# GECBalloonMCUFlightBoard_REV2_0_11-23-18.net
KiCad netlist of a schematic drawn in EAGLE
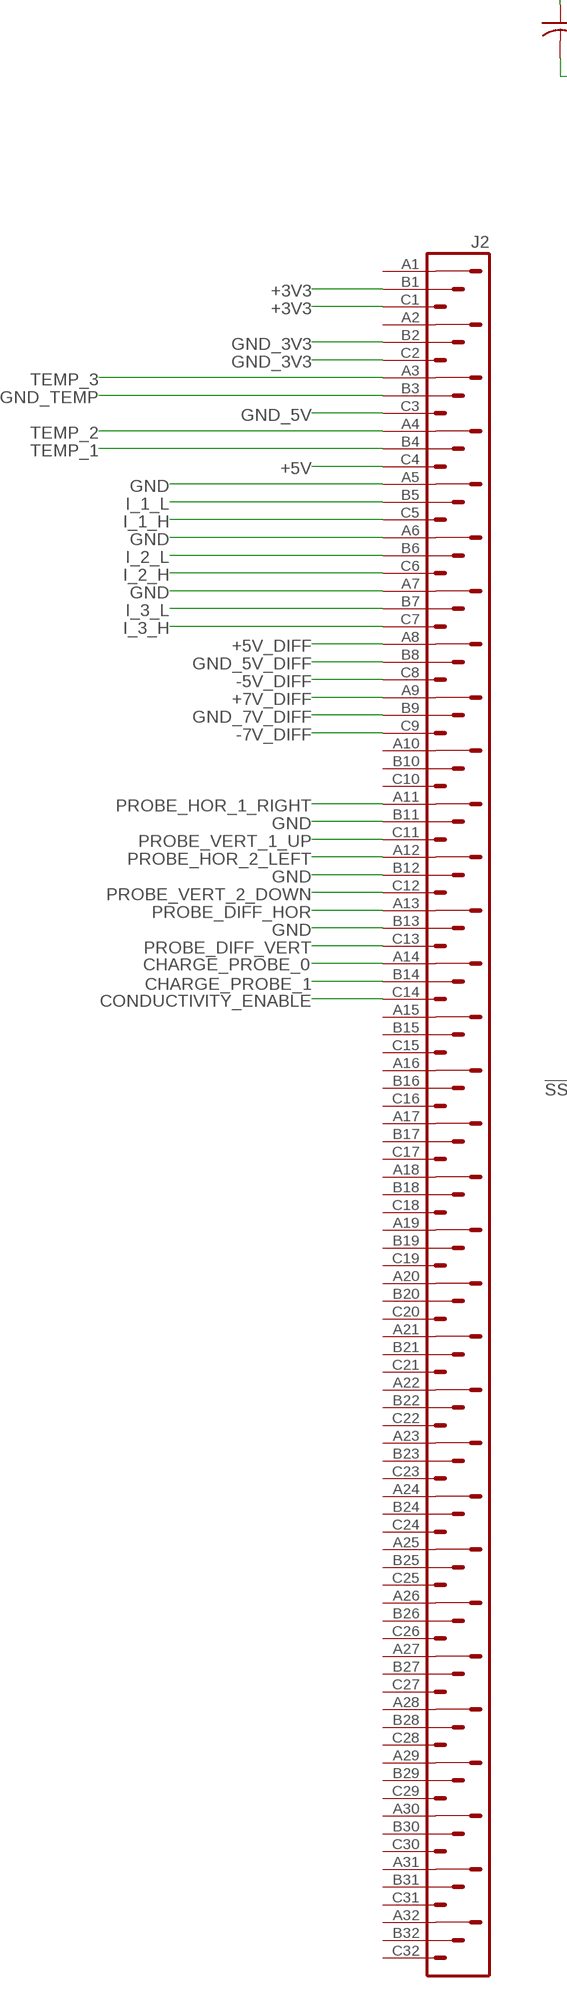
[diagram p0: schematic, sheet 1, part 1 of 2]
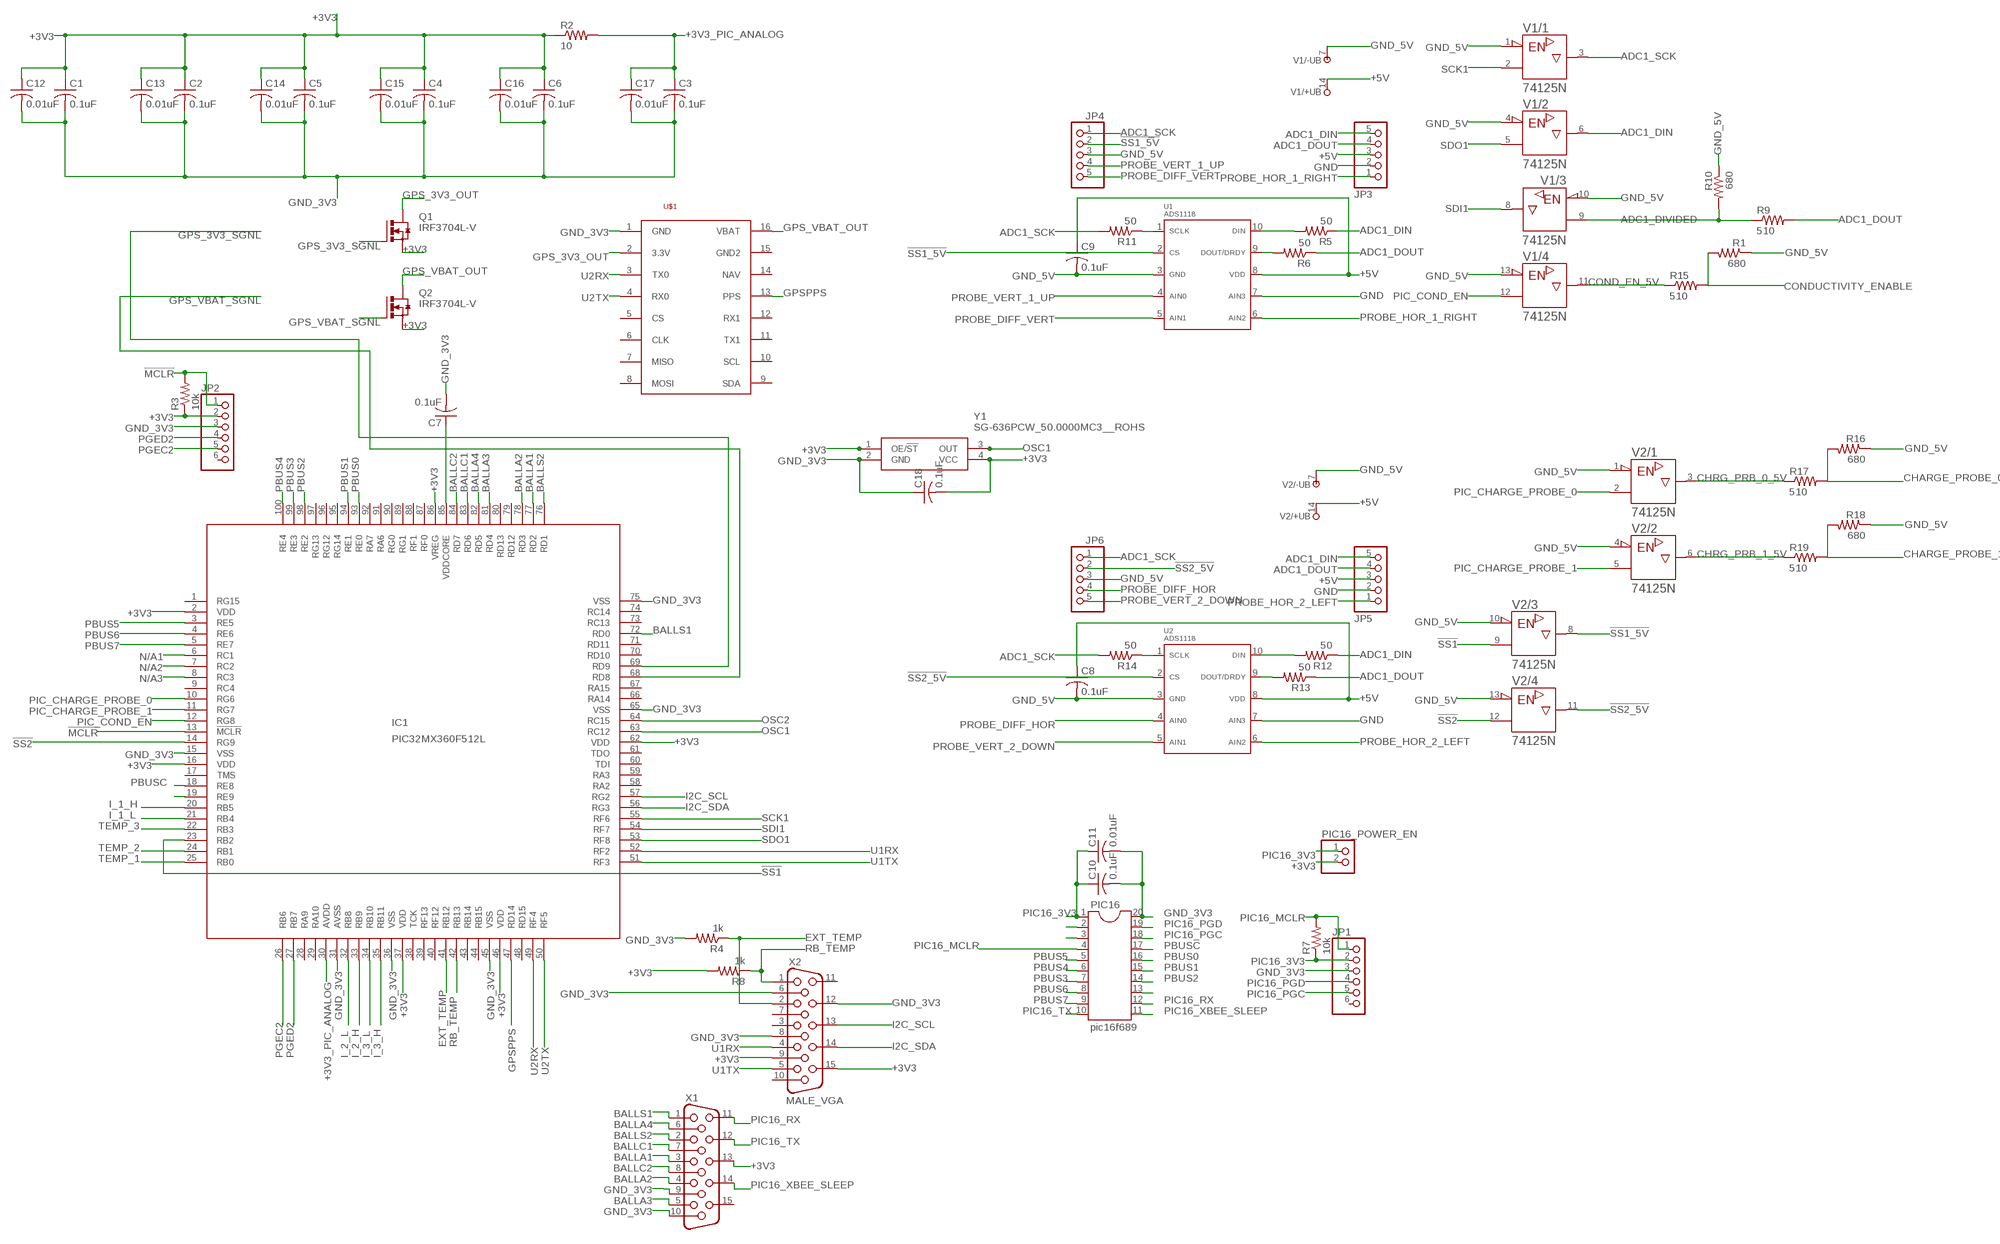
[diagram p1: schematic, sheet 1, part 2 of 2]

(export (version "E")
  (design (tool "Eeschema 10.0.6"))
  (components
    (comp (ref "C1")
      (value "0.1uF")
      (footprint "eagle-import:C1206")
      (libsource (lib "eagle-import") (part "C-USC1206"))
    )
    (comp (ref "C2")
      (value "0.1uF")
      (footprint "eagle-import:C1206")
      (libsource (lib "eagle-import") (part "C-USC1206"))
    )
    (comp (ref "C3")
      (value "0.1uF")
      (footprint "eagle-import:C1206")
      (libsource (lib "eagle-import") (part "C-USC1206"))
    )
    (comp (ref "C4")
      (value "0.1uF")
      (footprint "eagle-import:C1206")
      (libsource (lib "eagle-import") (part "C-USC1206"))
    )
    (comp (ref "C5")
      (value "0.1uF")
      (footprint "eagle-import:C1206")
      (libsource (lib "eagle-import") (part "C-USC1206"))
    )
    (comp (ref "C6")
      (value "0.1uF")
      (footprint "eagle-import:C1206")
      (libsource (lib "eagle-import") (part "C-USC1206"))
    )
    (comp (ref "C7")
      (value "0.1uF")
      (footprint "eagle-import:C1206")
      (libsource (lib "eagle-import") (part "C-USC1206"))
    )
    (comp (ref "C8")
      (value "0.1uF")
      (footprint "eagle-import:C1206")
      (libsource (lib "eagle-import") (part "C-USC1206"))
    )
    (comp (ref "C9")
      (value "0.1uF")
      (footprint "eagle-import:C1206")
      (libsource (lib "eagle-import") (part "C-USC1206"))
    )
    (comp (ref "C10")
      (value "0.1uF")
      (footprint "eagle-import:C1206")
      (libsource (lib "eagle-import") (part "C-USC1206"))
    )
    (comp (ref "C11")
      (value "0.01uF")
      (footprint "eagle-import:C1206")
      (libsource (lib "eagle-import") (part "C-USC1206"))
    )
    (comp (ref "C12")
      (value "0.01uF")
      (footprint "eagle-import:C1206")
      (libsource (lib "eagle-import") (part "C-USC1206"))
    )
    (comp (ref "C13")
      (value "0.01uF")
      (footprint "eagle-import:C1206")
      (libsource (lib "eagle-import") (part "C-USC1206"))
    )
    (comp (ref "C14")
      (value "0.01uF")
      (footprint "eagle-import:C1206")
      (libsource (lib "eagle-import") (part "C-USC1206"))
    )
    (comp (ref "C15")
      (value "0.01uF")
      (footprint "eagle-import:C1206")
      (libsource (lib "eagle-import") (part "C-USC1206"))
    )
    (comp (ref "C16")
      (value "0.01uF")
      (footprint "eagle-import:C1206")
      (libsource (lib "eagle-import") (part "C-USC1206"))
    )
    (comp (ref "C17")
      (value "0.01uF")
      (footprint "eagle-import:C1206")
      (libsource (lib "eagle-import") (part "C-USC1206"))
    )
    (comp (ref "C18")
      (value "0.1uF")
      (footprint "eagle-import:C1206")
      (libsource (lib "eagle-import") (part "C-USC1206"))
    )
    (comp (ref "IC1")
      (value "PIC32MX360F512L")
      (footprint "eagle-import:TQFP100")
      (libsource (lib "eagle-import") (part "PIC32MX360F512L"))
    )
    (comp (ref "J2")
      (value "VG96KB")
      (footprint "eagle-import:VG96KB")
      (libsource (lib "eagle-import") (part "VG96KB"))
    )
    (comp (ref "JP1")
      (value "PINHD-1X6")
      (footprint "eagle-import:1X06")
      (libsource (lib "eagle-import") (part "PINHD-1X6"))
    )
    (comp (ref "JP2")
      (value "PINHD-1X6")
      (footprint "eagle-import:1X06")
      (libsource (lib "eagle-import") (part "PINHD-1X6"))
    )
    (comp (ref "JP3")
      (value "PINHD-1X5")
      (footprint "eagle-import:1X05")
      (libsource (lib "eagle-import") (part "PINHD-1X5"))
    )
    (comp (ref "JP4")
      (value "PINHD-1X5")
      (footprint "eagle-import:1X05")
      (libsource (lib "eagle-import") (part "PINHD-1X5"))
    )
    (comp (ref "JP5")
      (value "PINHD-1X5")
      (footprint "eagle-import:1X05")
      (libsource (lib "eagle-import") (part "PINHD-1X5"))
    )
    (comp (ref "JP6")
      (value "PINHD-1X5")
      (footprint "eagle-import:1X05")
      (libsource (lib "eagle-import") (part "PINHD-1X5"))
    )
    (comp (ref "PIC16")
      (value "pic16f689")
      (footprint "eagle-import:DIL20")
      (libsource (lib "eagle-import") (part "DIL20"))
    )
    (comp (ref "PIC16_POWER_EN")
      (value "PINHD-1X2")
      (footprint "eagle-import:1X02")
      (libsource (lib "eagle-import") (part "PINHD-1X2"))
    )
    (comp (ref "Q1")
      (value "IRF3704L-V")
      (footprint "eagle-import:TO262-V")
      (libsource (lib "eagle-import") (part "IRF3704L-V"))
    )
    (comp (ref "Q2")
      (value "IRF3704L-V")
      (footprint "eagle-import:TO262-V")
      (libsource (lib "eagle-import") (part "IRF3704L-V"))
    )
    (comp (ref "R1")
      (value "680")
      (footprint "eagle-import:R1206")
      (libsource (lib "eagle-import") (part "resistor_R-US_R1206"))
    )
    (comp (ref "R2")
      (value "10")
      (footprint "eagle-import:M1206")
      (libsource (lib "eagle-import") (part "R-US_M1206"))
    )
    (comp (ref "R3")
      (value "10k")
      (footprint "eagle-import:M1206")
      (libsource (lib "eagle-import") (part "R-US_M1206"))
    )
    (comp (ref "R4")
      (value "1k")
      (footprint "eagle-import:0414_15")
      (libsource (lib "eagle-import") (part "resistor_R-US_0414/15"))
    )
    (comp (ref "R5")
      (value "50")
      (footprint "eagle-import:M1206")
      (libsource (lib "eagle-import") (part "R-US_M1206"))
    )
    (comp (ref "R6")
      (value "50")
      (footprint "eagle-import:M1206")
      (libsource (lib "eagle-import") (part "R-US_M1206"))
    )
    (comp (ref "R7")
      (value "10k")
      (footprint "eagle-import:M1206")
      (libsource (lib "eagle-import") (part "R-US_M1206"))
    )
    (comp (ref "R8")
      (value "1k")
      (footprint "eagle-import:0414_15")
      (libsource (lib "eagle-import") (part "resistor_R-US_0414/15"))
    )
    (comp (ref "R9")
      (value "510")
      (footprint "eagle-import:R1206")
      (libsource (lib "eagle-import") (part "resistor_R-US_R1206"))
    )
    (comp (ref "R10")
      (value "680")
      (footprint "eagle-import:R1206")
      (libsource (lib "eagle-import") (part "resistor_R-US_R1206"))
    )
    (comp (ref "R11")
      (value "50")
      (footprint "eagle-import:M1206")
      (libsource (lib "eagle-import") (part "R-US_M1206"))
    )
    (comp (ref "R12")
      (value "50")
      (footprint "eagle-import:M1206")
      (libsource (lib "eagle-import") (part "R-US_M1206"))
    )
    (comp (ref "R13")
      (value "50")
      (footprint "eagle-import:M1206")
      (libsource (lib "eagle-import") (part "R-US_M1206"))
    )
    (comp (ref "R14")
      (value "50")
      (footprint "eagle-import:M1206")
      (libsource (lib "eagle-import") (part "R-US_M1206"))
    )
    (comp (ref "R15")
      (value "510")
      (footprint "eagle-import:R1206")
      (libsource (lib "eagle-import") (part "resistor_R-US_R1206"))
    )
    (comp (ref "R16")
      (value "680")
      (footprint "eagle-import:R1206")
      (libsource (lib "eagle-import") (part "resistor_R-US_R1206"))
    )
    (comp (ref "R17")
      (value "510")
      (footprint "eagle-import:R1206")
      (libsource (lib "eagle-import") (part "resistor_R-US_R1206"))
    )
    (comp (ref "R18")
      (value "680")
      (footprint "eagle-import:R1206")
      (libsource (lib "eagle-import") (part "resistor_R-US_R1206"))
    )
    (comp (ref "R19")
      (value "510")
      (footprint "eagle-import:R1206")
      (libsource (lib "eagle-import") (part "resistor_R-US_R1206"))
    )
    (comp (ref "U$1")
      (value "SPARKFUN_VENUS_GPS_BREAKOUT")
      (footprint "eagle-import:SPARKFUN_BOARD")
      (libsource (lib "eagle-import") (part "SPARKFUN_VENUS_GPS_BREAKOUT"))
    )
    (comp (ref "U1")
      (value "ADS1118")
      (footprint "eagle-import:MSOP10")
      (libsource (lib "eagle-import") (part "ADS1118_MSOP10"))
    )
    (comp (ref "U2")
      (value "ADS1118")
      (footprint "eagle-import:MSOP10")
      (libsource (lib "eagle-import") (part "ADS1118_MSOP10"))
    )
    (comp (ref "V1")
      (value "74125N")
      (footprint "eagle-import:DIL14")
      (libsource (lib "eagle-import") (part "74125N"))
    )
    (comp (ref "V2")
      (value "74125N")
      (footprint "eagle-import:DIL14")
      (libsource (lib "eagle-import") (part "74125N"))
    )
    (comp (ref "X1")
      (value "HF15H")
      (footprint "eagle-import:HDF15H")
      (libsource (lib "eagle-import") (part "HF15H"))
    )
    (comp (ref "X2")
      (value "MALE_VGA")
      (footprint "eagle-import:MALE_PACKAGE")
      (libsource (lib "eagle-import") (part "MALE_VGA"))
    )
    (comp (ref "Y1")
      (value "SG-636PCW_50.0000MC3__ROHS")
      (footprint "eagle-import:SG-636")
      (fields (field (name "ARROW_PART_NUMBER") "SG-636PCW 50.0000MC3: ROHS"))
      (libsource (lib "eagle-import") (part "SG-636PCW_50.0000MC3__ROHS"))
    )
  )
  (nets
    (net (code "1") (name "/+3V3") (class "Default")
      (node (ref "C1") (pin "1") (pinfunction "1_1") (pintype "passive"))
      (node (ref "C12") (pin "1") (pinfunction "1_1") (pintype "passive"))
      (node (ref "C13") (pin "1") (pinfunction "1_1") (pintype "passive"))
      (node (ref "C14") (pin "1") (pinfunction "1_1") (pintype "passive"))
      (node (ref "C15") (pin "1") (pinfunction "1_1") (pintype "passive"))
      (node (ref "C16") (pin "1") (pinfunction "1_1") (pintype "passive"))
      (node (ref "C18") (pin "2") (pinfunction "2_2") (pintype "passive"))
      (node (ref "C2") (pin "1") (pinfunction "1_1") (pintype "passive"))
      (node (ref "C4") (pin "1") (pinfunction "1_1") (pintype "passive"))
      (node (ref "C5") (pin "1") (pinfunction "1_1") (pintype "passive"))
      (node (ref "C6") (pin "1") (pinfunction "1_1") (pintype "passive"))
      (node (ref "IC1") (pin "16") (pinfunction "VDD_16") (pintype "power_in"))
      (node (ref "IC1") (pin "2") (pinfunction "VDD_2") (pintype "power_in"))
      (node (ref "IC1") (pin "37") (pinfunction "VDD_37") (pintype "power_in"))
      (node (ref "IC1") (pin "46") (pinfunction "VDD_46") (pintype "power_in"))
      (node (ref "IC1") (pin "62") (pinfunction "VDD_62") (pintype "power_in"))
      (node (ref "IC1") (pin "86") (pinfunction "VREG_86") (pintype "passive"))
      (node (ref "J2") (pin "B1") (pinfunction "B1_B1") (pintype "passive"))
      (node (ref "J2") (pin "C1") (pinfunction "C1_C1") (pintype "passive"))
      (node (ref "JP2") (pin "2") (pinfunction "2_2") (pintype "passive"))
      (node (ref "PIC16_POWER_EN") (pin "2") (pinfunction "2_2") (pintype "passive"))
      (node (ref "Q1") (pin "3") (pinfunction "S_3") (pintype "passive"))
      (node (ref "Q2") (pin "3") (pinfunction "S_3") (pintype "passive"))
      (node (ref "R2") (pin "1") (pinfunction "1_1") (pintype "passive"))
      (node (ref "R3") (pin "1") (pinfunction "1_1") (pintype "passive"))
      (node (ref "R8") (pin "2") (pinfunction "2_2") (pintype "passive"))
      (node (ref "X1") (pin "13") (pinfunction "13_13") (pintype "passive"))
      (node (ref "X2") (pin "15") (pinfunction "15_15") (pintype "passive"))
      (node (ref "X2") (pin "9") (pinfunction "9_9") (pintype "passive"))
      (node (ref "Y1") (pin "1") (pinfunction "OE/~{ST}_1") (pintype "input"))
      (node (ref "Y1") (pin "4") (pinfunction "VCC_4") (pintype "power_in"))
    )
    (net (code "2") (name "/+3V3_PIC_ANALOG") (class "Default")
      (node (ref "C17") (pin "1") (pinfunction "1_1") (pintype "passive"))
      (node (ref "C3") (pin "1") (pinfunction "1_1") (pintype "passive"))
      (node (ref "IC1") (pin "30") (pinfunction "AVDD_30") (pintype "power_in"))
      (node (ref "R2") (pin "2") (pinfunction "2_2") (pintype "passive"))
    )
    (net (code "3") (name "/+5V") (class "Default")
      (node (ref "C8") (pin "1") (pinfunction "1_1") (pintype "passive"))
      (node (ref "C9") (pin "1") (pinfunction "1_1") (pintype "passive"))
      (node (ref "J2") (pin "C4") (pinfunction "C4_C4") (pintype "passive"))
      (node (ref "JP3") (pin "3") (pinfunction "3_3") (pintype "passive"))
      (node (ref "JP5") (pin "3") (pinfunction "3_3") (pintype "passive"))
      (node (ref "U1") (pin "8") (pinfunction "VDD_8") (pintype "bidirectional"))
      (node (ref "U2") (pin "8") (pinfunction "VDD_8") (pintype "bidirectional"))
      (node (ref "V1") (pin "14") (pinfunction "+UB_14") (pintype "power_in"))
      (node (ref "V2") (pin "14") (pinfunction "+UB_14") (pintype "power_in"))
    )
    (net (code "4") (name "/+5V_DIFF") (class "Default")
      (node (ref "J2") (pin "A8") (pinfunction "A8_A8") (pintype "passive"))
    )
    (net (code "5") (name "/+7V_DIFF") (class "Default")
      (node (ref "J2") (pin "A9") (pinfunction "A9_A9") (pintype "passive"))
    )
    (net (code "6") (name "/-5V_DIFF") (class "Default")
      (node (ref "J2") (pin "C8") (pinfunction "C8_C8") (pintype "passive"))
    )
    (net (code "7") (name "/-7V_DIFF") (class "Default")
      (node (ref "J2") (pin "C9") (pinfunction "C9_C9") (pintype "passive"))
    )
    (net (code "8") (name "/ADC1_DIN") (class "Default")
      (node (ref "JP3") (pin "5") (pinfunction "5_5") (pintype "passive"))
      (node (ref "JP5") (pin "5") (pinfunction "5_5") (pintype "passive"))
      (node (ref "R12") (pin "1") (pinfunction "1_1") (pintype "passive"))
      (node (ref "R5") (pin "1") (pinfunction "1_1") (pintype "passive"))
      (node (ref "V1") (pin "6") (pinfunction "Y_6") (pintype "tri_state"))
    )
    (net (code "9") (name "/ADC1_DIVIDED") (class "Default")
      (node (ref "R10") (pin "2") (pinfunction "2_2") (pintype "passive"))
      (node (ref "R9") (pin "1") (pinfunction "1_1") (pintype "passive"))
      (node (ref "V1") (pin "9") (pinfunction "A_9") (pintype "input"))
    )
    (net (code "10") (name "/ADC1_DOUT") (class "Default")
      (node (ref "JP3") (pin "4") (pinfunction "4_4") (pintype "passive"))
      (node (ref "JP5") (pin "4") (pinfunction "4_4") (pintype "passive"))
      (node (ref "R13") (pin "1") (pinfunction "1_1") (pintype "passive"))
      (node (ref "R6") (pin "1") (pinfunction "1_1") (pintype "passive"))
      (node (ref "R9") (pin "2") (pinfunction "2_2") (pintype "passive"))
    )
    (net (code "11") (name "/ADC1_SCK") (class "Default")
      (node (ref "JP4") (pin "1") (pinfunction "1_1") (pintype "passive"))
      (node (ref "JP6") (pin "1") (pinfunction "1_1") (pintype "passive"))
      (node (ref "R11") (pin "2") (pinfunction "2_2") (pintype "passive"))
      (node (ref "R14") (pin "2") (pinfunction "2_2") (pintype "passive"))
      (node (ref "V1") (pin "3") (pinfunction "Y_3") (pintype "tri_state"))
    )
    (net (code "12") (name "/BALLA1") (class "Default")
      (node (ref "IC1") (pin "77") (pinfunction "RD2_77") (pintype "bidirectional"))
      (node (ref "X1") (pin "3") (pinfunction "3_3") (pintype "passive"))
    )
    (net (code "13") (name "/BALLA2") (class "Default")
      (node (ref "IC1") (pin "78") (pinfunction "RD3_78") (pintype "bidirectional"))
      (node (ref "X1") (pin "4") (pinfunction "4_4") (pintype "passive"))
    )
    (net (code "14") (name "/BALLA3") (class "Default")
      (node (ref "IC1") (pin "81") (pinfunction "RD4_81") (pintype "bidirectional"))
      (node (ref "X1") (pin "5") (pinfunction "5_5") (pintype "passive"))
    )
    (net (code "15") (name "/BALLA4") (class "Default")
      (node (ref "IC1") (pin "82") (pinfunction "RD5_82") (pintype "bidirectional"))
      (node (ref "X1") (pin "6") (pinfunction "6_6") (pintype "passive"))
    )
    (net (code "16") (name "/BALLC1") (class "Default")
      (node (ref "IC1") (pin "83") (pinfunction "RD6_83") (pintype "bidirectional"))
      (node (ref "X1") (pin "7") (pinfunction "7_7") (pintype "passive"))
    )
    (net (code "17") (name "/BALLC2") (class "Default")
      (node (ref "IC1") (pin "84") (pinfunction "RD7_84") (pintype "bidirectional"))
      (node (ref "X1") (pin "8") (pinfunction "8_8") (pintype "passive"))
    )
    (net (code "18") (name "/BALLS1") (class "Default")
      (node (ref "IC1") (pin "72") (pinfunction "RD0_72") (pintype "bidirectional"))
      (node (ref "X1") (pin "1") (pinfunction "1_1") (pintype "passive"))
    )
    (net (code "19") (name "/BALLS2") (class "Default")
      (node (ref "IC1") (pin "76") (pinfunction "RD1_76") (pintype "bidirectional"))
      (node (ref "X1") (pin "2") (pinfunction "2_2") (pintype "passive"))
    )
    (net (code "20") (name "/CHARGE_PROBE_0") (class "Default")
      (node (ref "J2") (pin "A14") (pinfunction "A14_A14") (pintype "passive"))
      (node (ref "R16") (pin "2") (pinfunction "2_2") (pintype "passive"))
      (node (ref "R17") (pin "2") (pinfunction "2_2") (pintype "passive"))
    )
    (net (code "21") (name "/CHARGE_PROBE_1") (class "Default")
      (node (ref "J2") (pin "B14") (pinfunction "B14_B14") (pintype "passive"))
      (node (ref "R18") (pin "2") (pinfunction "2_2") (pintype "passive"))
      (node (ref "R19") (pin "2") (pinfunction "2_2") (pintype "passive"))
    )
    (net (code "22") (name "/CHRG_PRB_0_5V") (class "Default")
      (node (ref "R17") (pin "1") (pinfunction "1_1") (pintype "passive"))
      (node (ref "V2") (pin "3") (pinfunction "Y_3") (pintype "tri_state"))
    )
    (net (code "23") (name "/CHRG_PRB_1_5V") (class "Default")
      (node (ref "R19") (pin "1") (pinfunction "1_1") (pintype "passive"))
      (node (ref "V2") (pin "6") (pinfunction "Y_6") (pintype "tri_state"))
    )
    (net (code "24") (name "/CONDUCTIVITY_ENABLE") (class "Default")
      (node (ref "J2") (pin "C14") (pinfunction "C14_C14") (pintype "passive"))
      (node (ref "R1") (pin "2") (pinfunction "2_2") (pintype "passive"))
      (node (ref "R15") (pin "2") (pinfunction "2_2") (pintype "passive"))
    )
    (net (code "25") (name "/COND_EN_5V") (class "Default")
      (node (ref "R15") (pin "1") (pinfunction "1_1") (pintype "passive"))
      (node (ref "V1") (pin "11") (pinfunction "Y_11") (pintype "tri_state"))
    )
    (net (code "26") (name "/EXT_TEMP") (class "Default")
      (node (ref "IC1") (pin "41") (pinfunction "RB12_41") (pintype "bidirectional"))
      (node (ref "R4") (pin "1") (pinfunction "1_1") (pintype "passive"))
      (node (ref "X2") (pin "2") (pinfunction "2_2") (pintype "passive"))
    )
    (net (code "27") (name "/GND") (class "Default")
      (node (ref "J2") (pin "A5") (pinfunction "A5_A5") (pintype "passive"))
      (node (ref "J2") (pin "A6") (pinfunction "A6_A6") (pintype "passive"))
      (node (ref "J2") (pin "A7") (pinfunction "A7_A7") (pintype "passive"))
      (node (ref "J2") (pin "B11") (pinfunction "B11_B11") (pintype "passive"))
      (node (ref "J2") (pin "B12") (pinfunction "B12_B12") (pintype "passive"))
      (node (ref "J2") (pin "B13") (pinfunction "B13_B13") (pintype "passive"))
      (node (ref "JP3") (pin "2") (pinfunction "2_2") (pintype "passive"))
      (node (ref "JP5") (pin "2") (pinfunction "2_2") (pintype "passive"))
      (node (ref "U1") (pin "7") (pinfunction "AIN3_7") (pintype "bidirectional"))
      (node (ref "U2") (pin "7") (pinfunction "AIN3_7") (pintype "bidirectional"))
    )
    (net (code "28") (name "/GND_3V3") (class "Default")
      (node (ref "C1") (pin "2") (pinfunction "2_2") (pintype "passive"))
      (node (ref "C10") (pin "2") (pinfunction "2_2") (pintype "passive"))
      (node (ref "C11") (pin "2") (pinfunction "2_2") (pintype "passive"))
      (node (ref "C12") (pin "2") (pinfunction "2_2") (pintype "passive"))
      (node (ref "C13") (pin "2") (pinfunction "2_2") (pintype "passive"))
      (node (ref "C14") (pin "2") (pinfunction "2_2") (pintype "passive"))
      (node (ref "C15") (pin "2") (pinfunction "2_2") (pintype "passive"))
      (node (ref "C16") (pin "2") (pinfunction "2_2") (pintype "passive"))
      (node (ref "C17") (pin "2") (pinfunction "2_2") (pintype "passive"))
      (node (ref "C18") (pin "1") (pinfunction "1_1") (pintype "passive"))
      (node (ref "C2") (pin "2") (pinfunction "2_2") (pintype "passive"))
      (node (ref "C3") (pin "2") (pinfunction "2_2") (pintype "passive"))
      (node (ref "C4") (pin "2") (pinfunction "2_2") (pintype "passive"))
      (node (ref "C5") (pin "2") (pinfunction "2_2") (pintype "passive"))
      (node (ref "C6") (pin "2") (pinfunction "2_2") (pintype "passive"))
      (node (ref "C7") (pin "2") (pinfunction "2_2") (pintype "passive"))
      (node (ref "IC1") (pin "15") (pinfunction "VSS_15") (pintype "power_in"))
      (node (ref "IC1") (pin "31") (pinfunction "AVSS_31") (pintype "power_in"))
      (node (ref "IC1") (pin "36") (pinfunction "VSS_36") (pintype "power_in"))
      (node (ref "IC1") (pin "45") (pinfunction "VSS_45") (pintype "power_in"))
      (node (ref "IC1") (pin "65") (pinfunction "VSS_65") (pintype "power_in"))
      (node (ref "IC1") (pin "75") (pinfunction "VSS_75") (pintype "power_in"))
      (node (ref "J2") (pin "B2") (pinfunction "B2_B2") (pintype "passive"))
      (node (ref "J2") (pin "C2") (pinfunction "C2_C2") (pintype "passive"))
      (node (ref "JP1") (pin "3") (pinfunction "3_3") (pintype "passive"))
      (node (ref "JP2") (pin "3") (pinfunction "3_3") (pintype "passive"))
      (node (ref "PIC16") (pin "20") (pinfunction "20_20") (pintype "passive"))
      (node (ref "R4") (pin "2") (pinfunction "2_2") (pintype "passive"))
      (node (ref "U$1") (pin "1") (pinfunction "GND_1") (pintype "bidirectional"))
      (node (ref "X1") (pin "10") (pinfunction "10_10") (pintype "passive"))
      (node (ref "X1") (pin "9") (pinfunction "9_9") (pintype "passive"))
      (node (ref "X2") (pin "12") (pinfunction "12_12") (pintype "passive"))
      (node (ref "X2") (pin "6") (pinfunction "6_6") (pintype "passive"))
      (node (ref "X2") (pin "8") (pinfunction "8_8") (pintype "passive"))
      (node (ref "Y1") (pin "2") (pinfunction "GND_2") (pintype "power_in"))
    )
    (net (code "29") (name "/GND_5V") (class "Default")
      (node (ref "C8") (pin "2") (pinfunction "2_2") (pintype "passive"))
      (node (ref "C9") (pin "2") (pinfunction "2_2") (pintype "passive"))
      (node (ref "J2") (pin "C3") (pinfunction "C3_C3") (pintype "passive"))
      (node (ref "JP4") (pin "3") (pinfunction "3_3") (pintype "passive"))
      (node (ref "JP6") (pin "3") (pinfunction "3_3") (pintype "passive"))
      (node (ref "R1") (pin "1") (pinfunction "1_1") (pintype "passive"))
      (node (ref "R10") (pin "1") (pinfunction "1_1") (pintype "passive"))
      (node (ref "R16") (pin "1") (pinfunction "1_1") (pintype "passive"))
      (node (ref "R18") (pin "1") (pinfunction "1_1") (pintype "passive"))
      (node (ref "U1") (pin "3") (pinfunction "GND_3") (pintype "bidirectional"))
      (node (ref "U2") (pin "3") (pinfunction "GND_3") (pintype "bidirectional"))
      (node (ref "V1") (pin "1") (pinfunction "~{G}_1") (pintype "input"))
      (node (ref "V1") (pin "10") (pinfunction "~{G}_10") (pintype "input"))
      (node (ref "V1") (pin "13") (pinfunction "~{G}_13") (pintype "input"))
      (node (ref "V1") (pin "4") (pinfunction "~{G}_4") (pintype "input"))
      (node (ref "V1") (pin "7") (pinfunction "-UB_7") (pintype "power_in"))
      (node (ref "V2") (pin "1") (pinfunction "~{G}_1") (pintype "input"))
      (node (ref "V2") (pin "10") (pinfunction "~{G}_10") (pintype "input"))
      (node (ref "V2") (pin "13") (pinfunction "~{G}_13") (pintype "input"))
      (node (ref "V2") (pin "4") (pinfunction "~{G}_4") (pintype "input"))
      (node (ref "V2") (pin "7") (pinfunction "-UB_7") (pintype "power_in"))
    )
    (net (code "30") (name "/GND_5V_DIFF") (class "Default")
      (node (ref "J2") (pin "B8") (pinfunction "B8_B8") (pintype "passive"))
    )
    (net (code "31") (name "/GND_7V_DIFF") (class "Default")
      (node (ref "J2") (pin "B9") (pinfunction "B9_B9") (pintype "passive"))
    )
    (net (code "32") (name "/GND_TEMP") (class "Default")
      (node (ref "J2") (pin "B3") (pinfunction "B3_B3") (pintype "passive"))
    )
    (net (code "33") (name "/GPSPPS") (class "Default")
      (node (ref "IC1") (pin "47") (pinfunction "RD14_47") (pintype "bidirectional"))
      (node (ref "U$1") (pin "13") (pinfunction "PPS_13") (pintype "bidirectional"))
    )
    (net (code "34") (name "/GPS_3V3_OUT") (class "Default")
      (node (ref "Q1") (pin "2") (pinfunction "D_2") (pintype "passive"))
      (node (ref "U$1") (pin "2") (pinfunction "3.3V_2") (pintype "bidirectional"))
    )
    (net (code "35") (name "/GPS_3V3_SGNL") (class "Default")
      (node (ref "IC1") (pin "69") (pinfunction "RD9_69") (pintype "bidirectional"))
      (node (ref "Q1") (pin "1") (pinfunction "G_1") (pintype "passive"))
    )
    (net (code "36") (name "/GPS_VBAT_OUT") (class "Default")
      (node (ref "Q2") (pin "2") (pinfunction "D_2") (pintype "passive"))
      (node (ref "U$1") (pin "16") (pinfunction "VBAT_16") (pintype "bidirectional"))
    )
    (net (code "37") (name "/GPS_VBAT_SGNL") (class "Default")
      (node (ref "IC1") (pin "68") (pinfunction "RD8_68") (pintype "bidirectional"))
      (node (ref "Q2") (pin "1") (pinfunction "G_1") (pintype "passive"))
    )
    (net (code "38") (name "/I2C_SCL") (class "Default")
      (node (ref "IC1") (pin "57") (pinfunction "RG2_57") (pintype "bidirectional"))
      (node (ref "X2") (pin "13") (pinfunction "13_13") (pintype "passive"))
    )
    (net (code "39") (name "/I2C_SDA") (class "Default")
      (node (ref "IC1") (pin "56") (pinfunction "RG3_56") (pintype "bidirectional"))
      (node (ref "X2") (pin "14") (pinfunction "14_14") (pintype "passive"))
    )
    (net (code "40") (name "/I_1_H") (class "Default")
      (node (ref "IC1") (pin "20") (pinfunction "RB5_20") (pintype "bidirectional"))
      (node (ref "J2") (pin "C5") (pinfunction "C5_C5") (pintype "passive"))
    )
    (net (code "41") (name "/I_1_L") (class "Default")
      (node (ref "IC1") (pin "21") (pinfunction "RB4_21") (pintype "bidirectional"))
      (node (ref "J2") (pin "B5") (pinfunction "B5_B5") (pintype "passive"))
    )
    (net (code "42") (name "/I_2_H") (class "Default")
      (node (ref "IC1") (pin "33") (pinfunction "RB9_33") (pintype "bidirectional"))
      (node (ref "J2") (pin "C6") (pinfunction "C6_C6") (pintype "passive"))
    )
    (net (code "43") (name "/I_2_L") (class "Default")
      (node (ref "IC1") (pin "32") (pinfunction "RB8_32") (pintype "bidirectional"))
      (node (ref "J2") (pin "B6") (pinfunction "B6_B6") (pintype "passive"))
    )
    (net (code "44") (name "/I_3_H") (class "Default")
      (node (ref "IC1") (pin "35") (pinfunction "RB11_35") (pintype "bidirectional"))
      (node (ref "J2") (pin "C7") (pinfunction "C7_C7") (pintype "passive"))
    )
    (net (code "45") (name "/I_3_L") (class "Default")
      (node (ref "IC1") (pin "34") (pinfunction "RB10_34") (pintype "bidirectional"))
      (node (ref "J2") (pin "B7") (pinfunction "B7_B7") (pintype "passive"))
    )
    (net (code "46") (name "/N{slash}A1") (class "Default")
      (node (ref "IC1") (pin "6") (pinfunction "RC1_6") (pintype "bidirectional"))
    )
    (net (code "47") (name "/N{slash}A2") (class "Default")
      (node (ref "IC1") (pin "7") (pinfunction "RC2_7") (pintype "bidirectional"))
    )
    (net (code "48") (name "/N{slash}A3") (class "Default")
      (node (ref "IC1") (pin "8") (pinfunction "RC3_8") (pintype "bidirectional"))
    )
    (net (code "49") (name "/OSC1") (class "Default")
      (node (ref "IC1") (pin "63") (pinfunction "RC12_63") (pintype "bidirectional"))
      (node (ref "Y1") (pin "3") (pinfunction "OUT_3") (pintype "output"))
    )
    (net (code "50") (name "/OSC2") (class "Default")
      (node (ref "IC1") (pin "64") (pinfunction "RC15_64") (pintype "bidirectional"))
    )
    (net (code "51") (name "/PBUS0") (class "Default")
      (node (ref "IC1") (pin "93") (pinfunction "RE0_93") (pintype "bidirectional"))
      (node (ref "PIC16") (pin "16") (pinfunction "16_16") (pintype "passive"))
    )
    (net (code "52") (name "/PBUS1") (class "Default")
      (node (ref "IC1") (pin "94") (pinfunction "RE1_94") (pintype "bidirectional"))
      (node (ref "PIC16") (pin "15") (pinfunction "15_15") (pintype "passive"))
    )
    (net (code "53") (name "/PBUS2") (class "Default")
      (node (ref "IC1") (pin "98") (pinfunction "RE2_98") (pintype "bidirectional"))
      (node (ref "PIC16") (pin "14") (pinfunction "14_14") (pintype "passive"))
    )
    (net (code "54") (name "/PBUS3") (class "Default")
      (node (ref "IC1") (pin "99") (pinfunction "RE3_99") (pintype "bidirectional"))
      (node (ref "PIC16") (pin "7") (pinfunction "7_7") (pintype "passive"))
    )
    (net (code "55") (name "/PBUS4") (class "Default")
      (node (ref "IC1") (pin "100") (pinfunction "RE4_100") (pintype "bidirectional"))
      (node (ref "PIC16") (pin "6") (pinfunction "6_6") (pintype "passive"))
    )
    (net (code "56") (name "/PBUS5") (class "Default")
      (node (ref "IC1") (pin "3") (pinfunction "RE5_3") (pintype "bidirectional"))
      (node (ref "PIC16") (pin "5") (pinfunction "5_5") (pintype "passive"))
    )
    (net (code "57") (name "/PBUS6") (class "Default")
      (node (ref "IC1") (pin "4") (pinfunction "RE6_4") (pintype "bidirectional"))
      (node (ref "PIC16") (pin "8") (pinfunction "8_8") (pintype "passive"))
    )
    (net (code "58") (name "/PBUS7") (class "Default")
      (node (ref "IC1") (pin "5") (pinfunction "RE7_5") (pintype "bidirectional"))
      (node (ref "PIC16") (pin "9") (pinfunction "9_9") (pintype "passive"))
    )
    (net (code "59") (name "/PBUSC") (class "Default")
      (node (ref "IC1") (pin "18") (pinfunction "RE8_18") (pintype "bidirectional"))
      (node (ref "PIC16") (pin "17") (pinfunction "17_17") (pintype "passive"))
    )
    (net (code "60") (name "/PGEC2") (class "Default")
      (node (ref "IC1") (pin "26") (pinfunction "RB6_26") (pintype "bidirectional"))
      (node (ref "JP2") (pin "5") (pinfunction "5_5") (pintype "passive"))
    )
    (net (code "61") (name "/PGED2") (class "Default")
      (node (ref "IC1") (pin "27") (pinfunction "RB7_27") (pintype "bidirectional"))
      (node (ref "JP2") (pin "4") (pinfunction "4_4") (pintype "passive"))
    )
    (net (code "62") (name "/PIC16_3V3") (class "Default")
      (node (ref "C10") (pin "1") (pinfunction "1_1") (pintype "passive"))
      (node (ref "C11") (pin "1") (pinfunction "1_1") (pintype "passive"))
      (node (ref "JP1") (pin "2") (pinfunction "2_2") (pintype "passive"))
      (node (ref "PIC16") (pin "1") (pinfunction "1_1") (pintype "passive"))
      (node (ref "PIC16_POWER_EN") (pin "1") (pinfunction "1_1") (pintype "passive"))
      (node (ref "R7") (pin "1") (pinfunction "1_1") (pintype "passive"))
    )
    (net (code "63") (name "/PIC16_MCLR") (class "Default")
      (node (ref "JP1") (pin "1") (pinfunction "1_1") (pintype "passive"))
      (node (ref "PIC16") (pin "4") (pinfunction "4_4") (pintype "passive"))
      (node (ref "R7") (pin "2") (pinfunction "2_2") (pintype "passive"))
    )
    (net (code "64") (name "/PIC16_PGC") (class "Default")
      (node (ref "JP1") (pin "5") (pinfunction "5_5") (pintype "passive"))
      (node (ref "PIC16") (pin "18") (pinfunction "18_18") (pintype "passive"))
    )
    (net (code "65") (name "/PIC16_PGD") (class "Default")
      (node (ref "JP1") (pin "4") (pinfunction "4_4") (pintype "passive"))
      (node (ref "PIC16") (pin "19") (pinfunction "19_19") (pintype "passive"))
    )
    (net (code "66") (name "/PIC16_RX") (class "Default")
      (node (ref "PIC16") (pin "12") (pinfunction "12_12") (pintype "passive"))
      (node (ref "X1") (pin "11") (pinfunction "11_11") (pintype "passive"))
    )
    (net (code "67") (name "/PIC16_TX") (class "Default")
      (node (ref "PIC16") (pin "10") (pinfunction "10_10") (pintype "passive"))
      (node (ref "X1") (pin "12") (pinfunction "12_12") (pintype "passive"))
    )
    (net (code "68") (name "/PIC16_XBEE_SLEEP") (class "Default")
      (node (ref "PIC16") (pin "11") (pinfunction "11_11") (pintype "passive"))
      (node (ref "X1") (pin "14") (pinfunction "14_14") (pintype "passive"))
    )
    (net (code "69") (name "/PIC_CHARGE_PROBE_0") (class "Default")
      (node (ref "IC1") (pin "10") (pinfunction "RG6_10") (pintype "bidirectional"))
      (node (ref "V2") (pin "2") (pinfunction "A_2") (pintype "input"))
    )
    (net (code "70") (name "/PIC_CHARGE_PROBE_1") (class "Default")
      (node (ref "IC1") (pin "11") (pinfunction "RG7_11") (pintype "bidirectional"))
      (node (ref "V2") (pin "5") (pinfunction "A_5") (pintype "input"))
    )
    (net (code "71") (name "/PIC_COND_EN") (class "Default")
      (node (ref "IC1") (pin "12") (pinfunction "RG8_12") (pintype "bidirectional"))
      (node (ref "V1") (pin "12") (pinfunction "A_12") (pintype "input"))
    )
    (net (code "72") (name "/PROBE_DIFF_HOR") (class "Default")
      (node (ref "J2") (pin "A13") (pinfunction "A13_A13") (pintype "passive"))
      (node (ref "JP6") (pin "4") (pinfunction "4_4") (pintype "passive"))
      (node (ref "U2") (pin "4") (pinfunction "AIN0_4") (pintype "bidirectional"))
    )
    (net (code "73") (name "/PROBE_DIFF_VERT") (class "Default")
      (node (ref "J2") (pin "C13") (pinfunction "C13_C13") (pintype "passive"))
      (node (ref "JP4") (pin "5") (pinfunction "5_5") (pintype "passive"))
      (node (ref "U1") (pin "5") (pinfunction "AIN1_5") (pintype "bidirectional"))
    )
    (net (code "74") (name "/PROBE_HOR_1_RIGHT") (class "Default")
      (node (ref "J2") (pin "A11") (pinfunction "A11_A11") (pintype "passive"))
      (node (ref "JP3") (pin "1") (pinfunction "1_1") (pintype "passive"))
      (node (ref "U1") (pin "6") (pinfunction "AIN2_6") (pintype "bidirectional"))
    )
    (net (code "75") (name "/PROBE_HOR_2_LEFT") (class "Default")
      (node (ref "J2") (pin "A12") (pinfunction "A12_A12") (pintype "passive"))
      (node (ref "JP5") (pin "1") (pinfunction "1_1") (pintype "passive"))
      (node (ref "U2") (pin "6") (pinfunction "AIN2_6") (pintype "bidirectional"))
    )
    (net (code "76") (name "/PROBE_VERT_1_UP") (class "Default")
      (node (ref "J2") (pin "C11") (pinfunction "C11_C11") (pintype "passive"))
      (node (ref "JP4") (pin "4") (pinfunction "4_4") (pintype "passive"))
      (node (ref "U1") (pin "4") (pinfunction "AIN0_4") (pintype "bidirectional"))
    )
    (net (code "77") (name "/PROBE_VERT_2_DOWN") (class "Default")
      (node (ref "J2") (pin "C12") (pinfunction "C12_C12") (pintype "passive"))
      (node (ref "JP6") (pin "5") (pinfunction "5_5") (pintype "passive"))
      (node (ref "U2") (pin "5") (pinfunction "AIN1_5") (pintype "bidirectional"))
    )
    (net (code "78") (name "/RB_TEMP") (class "Default")
      (node (ref "IC1") (pin "42") (pinfunction "RB13_42") (pintype "bidirectional"))
      (node (ref "R8") (pin "1") (pinfunction "1_1") (pintype "passive"))
      (node (ref "X2") (pin "1") (pinfunction "1_1") (pintype "passive"))
    )
    (net (code "79") (name "/SCK1") (class "Default")
      (node (ref "IC1") (pin "55") (pinfunction "RF6_55") (pintype "bidirectional"))
      (node (ref "V1") (pin "2") (pinfunction "A_2") (pintype "input"))
    )
    (net (code "80") (name "/SDI1") (class "Default")
      (node (ref "IC1") (pin "54") (pinfunction "RF7_54") (pintype "bidirectional"))
      (node (ref "V1") (pin "8") (pinfunction "Y_8") (pintype "tri_state"))
    )
    (net (code "81") (name "/SDO1") (class "Default")
      (node (ref "IC1") (pin "53") (pinfunction "RF8_53") (pintype "bidirectional"))
      (node (ref "V1") (pin "5") (pinfunction "A_5") (pintype "input"))
    )
    (net (code "82") (name "/TEMP_1") (class "Default")
      (node (ref "IC1") (pin "25") (pinfunction "RB0_25") (pintype "bidirectional"))
      (node (ref "J2") (pin "B4") (pinfunction "B4_B4") (pintype "passive"))
    )
    (net (code "83") (name "/TEMP_2") (class "Default")
      (node (ref "IC1") (pin "24") (pinfunction "RB1_24") (pintype "bidirectional"))
      (node (ref "J2") (pin "A4") (pinfunction "A4_A4") (pintype "passive"))
    )
    (net (code "84") (name "/TEMP_3") (class "Default")
      (node (ref "IC1") (pin "22") (pinfunction "RB3_22") (pintype "bidirectional"))
      (node (ref "J2") (pin "A3") (pinfunction "A3_A3") (pintype "passive"))
    )
    (net (code "85") (name "/U1RX") (class "Default")
      (node (ref "IC1") (pin "52") (pinfunction "RF2_52") (pintype "bidirectional"))
      (node (ref "X2") (pin "4") (pinfunction "4_4") (pintype "passive"))
    )
    (net (code "86") (name "/U1TX") (class "Default")
      (node (ref "IC1") (pin "51") (pinfunction "RF3_51") (pintype "bidirectional"))
      (node (ref "X2") (pin "5") (pinfunction "5_5") (pintype "passive"))
    )
    (net (code "87") (name "/U2RX") (class "Default")
      (node (ref "IC1") (pin "49") (pinfunction "RF4_49") (pintype "bidirectional"))
      (node (ref "U$1") (pin "3") (pinfunction "TX0_3") (pintype "bidirectional"))
    )
    (net (code "88") (name "/U2TX") (class "Default")
      (node (ref "IC1") (pin "50") (pinfunction "RF5_50") (pintype "bidirectional"))
      (node (ref "U$1") (pin "4") (pinfunction "RX0_4") (pintype "bidirectional"))
    )
    (net (code "89") (name "/~{MCLR}") (class "Default")
      (node (ref "IC1") (pin "13") (pinfunction "~{MCLR}_13") (pintype "input"))
      (node (ref "JP2") (pin "1") (pinfunction "1_1") (pintype "passive"))
      (node (ref "R3") (pin "2") (pinfunction "2_2") (pintype "passive"))
    )
    (net (code "90") (name "/~{SS1_5V}") (class "Default")
      (node (ref "JP4") (pin "2") (pinfunction "2_2") (pintype "passive"))
      (node (ref "U1") (pin "2") (pinfunction "CS_2") (pintype "bidirectional"))
      (node (ref "V2") (pin "8") (pinfunction "Y_8") (pintype "tri_state"))
    )
    (net (code "91") (name "/~{SS1}") (class "Default")
      (node (ref "IC1") (pin "23") (pinfunction "RB2_23") (pintype "bidirectional"))
      (node (ref "V2") (pin "9") (pinfunction "A_9") (pintype "input"))
    )
    (net (code "92") (name "/~{SS2_5V}") (class "Default")
      (node (ref "JP6") (pin "2") (pinfunction "2_2") (pintype "passive"))
      (node (ref "U2") (pin "2") (pinfunction "CS_2") (pintype "bidirectional"))
      (node (ref "V2") (pin "11") (pinfunction "Y_11") (pintype "tri_state"))
    )
    (net (code "93") (name "/~{SS2}") (class "Default")
      (node (ref "IC1") (pin "14") (pinfunction "RG9_14") (pintype "bidirectional"))
      (node (ref "V2") (pin "12") (pinfunction "A_12") (pintype "input"))
    )
    (net (code "94") (name "Net-(IC1-VDDCORE)") (class "Default")
      (node (ref "C7") (pin "1") (pinfunction "1_1") (pintype "passive"))
      (node (ref "IC1") (pin "85") (pinfunction "VDDCORE_85") (pintype "power_in"))
    )
    (net (code "95") (name "Net-(U1-DIN)") (class "Default")
      (node (ref "R5") (pin "2") (pinfunction "2_2") (pintype "passive"))
      (node (ref "U1") (pin "10") (pinfunction "DIN_10") (pintype "bidirectional"))
    )
    (net (code "96") (name "Net-(U1-DOUT{slash}DRDY)") (class "Default")
      (node (ref "R6") (pin "2") (pinfunction "2_2") (pintype "passive"))
      (node (ref "U1") (pin "9") (pinfunction "DOUT/DRDY_9") (pintype "bidirectional"))
    )
    (net (code "97") (name "Net-(U1-SCLK)") (class "Default")
      (node (ref "R11") (pin "1") (pinfunction "1_1") (pintype "passive"))
      (node (ref "U1") (pin "1") (pinfunction "SCLK_1") (pintype "bidirectional"))
    )
    (net (code "98") (name "Net-(U2-DIN)") (class "Default")
      (node (ref "R12") (pin "2") (pinfunction "2_2") (pintype "passive"))
      (node (ref "U2") (pin "10") (pinfunction "DIN_10") (pintype "bidirectional"))
    )
    (net (code "99") (name "Net-(U2-DOUT{slash}DRDY)") (class "Default")
      (node (ref "R13") (pin "2") (pinfunction "2_2") (pintype "passive"))
      (node (ref "U2") (pin "9") (pinfunction "DOUT/DRDY_9") (pintype "bidirectional"))
    )
    (net (code "100") (name "Net-(U2-SCLK)") (class "Default")
      (node (ref "R14") (pin "1") (pinfunction "1_1") (pintype "passive"))
      (node (ref "U2") (pin "1") (pinfunction "SCLK_1") (pintype "bidirectional"))
    )
    (net (code "101") (name "unconnected-(IC1-RA2-Pad58)") (class "Default")
      (node (ref "IC1") (pin "58") (pinfunction "RA2_58") (pintype "bidirectional"))
    )
    (net (code "102") (name "unconnected-(IC1-RA3-Pad59)") (class "Default")
      (node (ref "IC1") (pin "59") (pinfunction "RA3_59") (pintype "bidirectional"))
    )
    (net (code "103") (name "unconnected-(IC1-RA6-Pad91)") (class "Default")
      (node (ref "IC1") (pin "91") (pinfunction "RA6_91") (pintype "bidirectional"))
    )
    (net (code "104") (name "unconnected-(IC1-RA7-Pad92)") (class "Default")
      (node (ref "IC1") (pin "92") (pinfunction "RA7_92") (pintype "bidirectional"))
    )
    (net (code "105") (name "unconnected-(IC1-RA9-Pad28)") (class "Default")
      (node (ref "IC1") (pin "28") (pinfunction "RA9_28") (pintype "bidirectional"))
    )
    (net (code "106") (name "unconnected-(IC1-RA10-Pad29)") (class "Default")
      (node (ref "IC1") (pin "29") (pinfunction "RA10_29") (pintype "bidirectional"))
    )
    (net (code "107") (name "unconnected-(IC1-RA14-Pad66)") (class "Default")
      (node (ref "IC1") (pin "66") (pinfunction "RA14_66") (pintype "bidirectional"))
    )
    (net (code "108") (name "unconnected-(IC1-RA15-Pad67)") (class "Default")
      (node (ref "IC1") (pin "67") (pinfunction "RA15_67") (pintype "bidirectional"))
    )
    (net (code "109") (name "unconnected-(IC1-RB14-Pad43)") (class "Default")
      (node (ref "IC1") (pin "43") (pinfunction "RB14_43") (pintype "bidirectional"))
    )
    (net (code "110") (name "unconnected-(IC1-RB15-Pad44)") (class "Default")
      (node (ref "IC1") (pin "44") (pinfunction "RB15_44") (pintype "bidirectional"))
    )
    (net (code "111") (name "unconnected-(IC1-RC4-Pad9)") (class "Default")
      (node (ref "IC1") (pin "9") (pinfunction "RC4_9") (pintype "bidirectional"))
    )
    (net (code "112") (name "unconnected-(IC1-RC13-Pad73)") (class "Default")
      (node (ref "IC1") (pin "73") (pinfunction "RC13_73") (pintype "bidirectional"))
    )
    (net (code "113") (name "unconnected-(IC1-RC14-Pad74)") (class "Default")
      (node (ref "IC1") (pin "74") (pinfunction "RC14_74") (pintype "bidirectional"))
    )
    (net (code "114") (name "unconnected-(IC1-RD10-Pad70)") (class "Default")
      (node (ref "IC1") (pin "70") (pinfunction "RD10_70") (pintype "bidirectional"))
    )
    (net (code "115") (name "unconnected-(IC1-RD11-Pad71)") (class "Default")
      (node (ref "IC1") (pin "71") (pinfunction "RD11_71") (pintype "bidirectional"))
    )
    (net (code "116") (name "unconnected-(IC1-RD12-Pad79)") (class "Default")
      (node (ref "IC1") (pin "79") (pinfunction "RD12_79") (pintype "bidirectional"))
    )
    (net (code "117") (name "unconnected-(IC1-RD13-Pad80)") (class "Default")
      (node (ref "IC1") (pin "80") (pinfunction "RD13_80") (pintype "bidirectional"))
    )
    (net (code "118") (name "unconnected-(IC1-RD15-Pad48)") (class "Default")
      (node (ref "IC1") (pin "48") (pinfunction "RD15_48") (pintype "bidirectional"))
    )
    (net (code "119") (name "unconnected-(IC1-RE9-Pad19)") (class "Default")
      (node (ref "IC1") (pin "19") (pinfunction "RE9_19") (pintype "bidirectional"))
    )
    (net (code "120") (name "unconnected-(IC1-RF0-Pad87)") (class "Default")
      (node (ref "IC1") (pin "87") (pinfunction "RF0_87") (pintype "bidirectional"))
    )
    (net (code "121") (name "unconnected-(IC1-RF1-Pad88)") (class "Default")
      (node (ref "IC1") (pin "88") (pinfunction "RF1_88") (pintype "bidirectional"))
    )
    (net (code "122") (name "unconnected-(IC1-RF12-Pad40)") (class "Default")
      (node (ref "IC1") (pin "40") (pinfunction "RF12_40") (pintype "bidirectional"))
    )
    (net (code "123") (name "unconnected-(IC1-RF13-Pad39)") (class "Default")
      (node (ref "IC1") (pin "39") (pinfunction "RF13_39") (pintype "bidirectional"))
    )
    (net (code "124") (name "unconnected-(IC1-RG0-Pad90)") (class "Default")
      (node (ref "IC1") (pin "90") (pinfunction "RG0_90") (pintype "bidirectional"))
    )
    (net (code "125") (name "unconnected-(IC1-RG1-Pad89)") (class "Default")
      (node (ref "IC1") (pin "89") (pinfunction "RG1_89") (pintype "bidirectional"))
    )
    (net (code "126") (name "unconnected-(IC1-RG12-Pad96)") (class "Default")
      (node (ref "IC1") (pin "96") (pinfunction "RG12_96") (pintype "bidirectional"))
    )
    (net (code "127") (name "unconnected-(IC1-RG13-Pad97)") (class "Default")
      (node (ref "IC1") (pin "97") (pinfunction "RG13_97") (pintype "bidirectional"))
    )
    (net (code "128") (name "unconnected-(IC1-RG14-Pad95)") (class "Default")
      (node (ref "IC1") (pin "95") (pinfunction "RG14_95") (pintype "bidirectional"))
    )
    (net (code "129") (name "unconnected-(IC1-RG15-Pad1)") (class "Default")
      (node (ref "IC1") (pin "1") (pinfunction "RG15_1") (pintype "bidirectional"))
    )
    (net (code "130") (name "unconnected-(IC1-TCK-Pad38)") (class "Default")
      (node (ref "IC1") (pin "38") (pinfunction "TCK_38") (pintype "input"))
    )
    (net (code "131") (name "unconnected-(IC1-TDI-Pad60)") (class "Default")
      (node (ref "IC1") (pin "60") (pinfunction "TDI_60") (pintype "input"))
    )
    (net (code "132") (name "unconnected-(IC1-TDO-Pad61)") (class "Default")
      (node (ref "IC1") (pin "61") (pinfunction "TDO_61") (pintype "output"))
    )
    (net (code "133") (name "unconnected-(IC1-TMS-Pad17)") (class "Default")
      (node (ref "IC1") (pin "17") (pinfunction "TMS_17") (pintype "input"))
    )
    (net (code "134") (name "unconnected-(J2-PadA1)") (class "Default")
      (node (ref "J2") (pin "A1") (pinfunction "A1_A1") (pintype "passive"))
    )
    (net (code "135") (name "unconnected-(J2-PadA2)") (class "Default")
      (node (ref "J2") (pin "A2") (pinfunction "A2_A2") (pintype "passive"))
    )
    (net (code "136") (name "unconnected-(J2-PadA10)") (class "Default")
      (node (ref "J2") (pin "A10") (pinfunction "A10_A10") (pintype "passive"))
    )
    (net (code "137") (name "unconnected-(J2-PadA15)") (class "Default")
      (node (ref "J2") (pin "A15") (pinfunction "A15_A15") (pintype "passive"))
    )
    (net (code "138") (name "unconnected-(J2-PadA16)") (class "Default")
      (node (ref "J2") (pin "A16") (pinfunction "A16_A16") (pintype "passive"))
    )
    (net (code "139") (name "unconnected-(J2-PadA17)") (class "Default")
      (node (ref "J2") (pin "A17") (pinfunction "A17_A17") (pintype "passive"))
    )
    (net (code "140") (name "unconnected-(J2-PadA18)") (class "Default")
      (node (ref "J2") (pin "A18") (pinfunction "A18_A18") (pintype "passive"))
    )
    (net (code "141") (name "unconnected-(J2-PadA19)") (class "Default")
      (node (ref "J2") (pin "A19") (pinfunction "A19_A19") (pintype "passive"))
    )
    (net (code "142") (name "unconnected-(J2-PadA20)") (class "Default")
      (node (ref "J2") (pin "A20") (pinfunction "A20_A20") (pintype "passive"))
    )
    (net (code "143") (name "unconnected-(J2-PadA21)") (class "Default")
      (node (ref "J2") (pin "A21") (pinfunction "A21_A21") (pintype "passive"))
    )
    (net (code "144") (name "unconnected-(J2-PadA22)") (class "Default")
      (node (ref "J2") (pin "A22") (pinfunction "A22_A22") (pintype "passive"))
    )
    (net (code "145") (name "unconnected-(J2-PadA23)") (class "Default")
      (node (ref "J2") (pin "A23") (pinfunction "A23_A23") (pintype "passive"))
    )
    (net (code "146") (name "unconnected-(J2-PadA24)") (class "Default")
      (node (ref "J2") (pin "A24") (pinfunction "A24_A24") (pintype "passive"))
    )
    (net (code "147") (name "unconnected-(J2-PadA25)") (class "Default")
      (node (ref "J2") (pin "A25") (pinfunction "A25_A25") (pintype "passive"))
    )
    (net (code "148") (name "unconnected-(J2-PadA26)") (class "Default")
      (node (ref "J2") (pin "A26") (pinfunction "A26_A26") (pintype "passive"))
    )
    (net (code "149") (name "unconnected-(J2-PadA27)") (class "Default")
      (node (ref "J2") (pin "A27") (pinfunction "A27_A27") (pintype "passive"))
    )
    (net (code "150") (name "unconnected-(J2-PadA28)") (class "Default")
      (node (ref "J2") (pin "A28") (pinfunction "A28_A28") (pintype "passive"))
    )
    (net (code "151") (name "unconnected-(J2-PadA29)") (class "Default")
      (node (ref "J2") (pin "A29") (pinfunction "A29_A29") (pintype "passive"))
    )
    (net (code "152") (name "unconnected-(J2-PadA30)") (class "Default")
      (node (ref "J2") (pin "A30") (pinfunction "A30_A30") (pintype "passive"))
    )
    (net (code "153") (name "unconnected-(J2-PadA31)") (class "Default")
      (node (ref "J2") (pin "A31") (pinfunction "A31_A31") (pintype "passive"))
    )
    (net (code "154") (name "unconnected-(J2-PadA32)") (class "Default")
      (node (ref "J2") (pin "A32") (pinfunction "A32_A32") (pintype "passive"))
    )
    (net (code "155") (name "unconnected-(J2-PadB10)") (class "Default")
      (node (ref "J2") (pin "B10") (pinfunction "B10_B10") (pintype "passive"))
    )
    (net (code "156") (name "unconnected-(J2-PadB15)") (class "Default")
      (node (ref "J2") (pin "B15") (pinfunction "B15_B15") (pintype "passive"))
    )
    (net (code "157") (name "unconnected-(J2-PadB16)") (class "Default")
      (node (ref "J2") (pin "B16") (pinfunction "B16_B16") (pintype "passive"))
    )
    (net (code "158") (name "unconnected-(J2-PadB17)") (class "Default")
      (node (ref "J2") (pin "B17") (pinfunction "B17_B17") (pintype "passive"))
    )
    (net (code "159") (name "unconnected-(J2-PadB18)") (class "Default")
      (node (ref "J2") (pin "B18") (pinfunction "B18_B18") (pintype "passive"))
    )
    (net (code "160") (name "unconnected-(J2-PadB19)") (class "Default")
      (node (ref "J2") (pin "B19") (pinfunction "B19_B19") (pintype "passive"))
    )
    (net (code "161") (name "unconnected-(J2-PadB20)") (class "Default")
      (node (ref "J2") (pin "B20") (pinfunction "B20_B20") (pintype "passive"))
    )
    (net (code "162") (name "unconnected-(J2-PadB21)") (class "Default")
      (node (ref "J2") (pin "B21") (pinfunction "B21_B21") (pintype "passive"))
    )
    (net (code "163") (name "unconnected-(J2-PadB22)") (class "Default")
      (node (ref "J2") (pin "B22") (pinfunction "B22_B22") (pintype "passive"))
    )
    (net (code "164") (name "unconnected-(J2-PadB23)") (class "Default")
      (node (ref "J2") (pin "B23") (pinfunction "B23_B23") (pintype "passive"))
    )
    (net (code "165") (name "unconnected-(J2-PadB24)") (class "Default")
      (node (ref "J2") (pin "B24") (pinfunction "B24_B24") (pintype "passive"))
    )
    (net (code "166") (name "unconnected-(J2-PadB25)") (class "Default")
      (node (ref "J2") (pin "B25") (pinfunction "B25_B25") (pintype "passive"))
    )
    (net (code "167") (name "unconnected-(J2-PadB26)") (class "Default")
      (node (ref "J2") (pin "B26") (pinfunction "B26_B26") (pintype "passive"))
    )
    (net (code "168") (name "unconnected-(J2-PadB27)") (class "Default")
      (node (ref "J2") (pin "B27") (pinfunction "B27_B27") (pintype "passive"))
    )
    (net (code "169") (name "unconnected-(J2-PadB28)") (class "Default")
      (node (ref "J2") (pin "B28") (pinfunction "B28_B28") (pintype "passive"))
    )
    (net (code "170") (name "unconnected-(J2-PadB29)") (class "Default")
      (node (ref "J2") (pin "B29") (pinfunction "B29_B29") (pintype "passive"))
    )
    (net (code "171") (name "unconnected-(J2-PadB30)") (class "Default")
      (node (ref "J2") (pin "B30") (pinfunction "B30_B30") (pintype "passive"))
    )
    (net (code "172") (name "unconnected-(J2-PadB31)") (class "Default")
      (node (ref "J2") (pin "B31") (pinfunction "B31_B31") (pintype "passive"))
    )
    (net (code "173") (name "unconnected-(J2-PadB32)") (class "Default")
      (node (ref "J2") (pin "B32") (pinfunction "B32_B32") (pintype "passive"))
    )
    (net (code "174") (name "unconnected-(J2-PadC10)") (class "Default")
      (node (ref "J2") (pin "C10") (pinfunction "C10_C10") (pintype "passive"))
    )
    (net (code "175") (name "unconnected-(J2-PadC15)") (class "Default")
      (node (ref "J2") (pin "C15") (pinfunction "C15_C15") (pintype "passive"))
    )
    (net (code "176") (name "unconnected-(J2-PadC16)") (class "Default")
      (node (ref "J2") (pin "C16") (pinfunction "C16_C16") (pintype "passive"))
    )
    (net (code "177") (name "unconnected-(J2-PadC17)") (class "Default")
      (node (ref "J2") (pin "C17") (pinfunction "C17_C17") (pintype "passive"))
    )
    (net (code "178") (name "unconnected-(J2-PadC18)") (class "Default")
      (node (ref "J2") (pin "C18") (pinfunction "C18_C18") (pintype "passive"))
    )
    (net (code "179") (name "unconnected-(J2-PadC19)") (class "Default")
      (node (ref "J2") (pin "C19") (pinfunction "C19_C19") (pintype "passive"))
    )
    (net (code "180") (name "unconnected-(J2-PadC20)") (class "Default")
      (node (ref "J2") (pin "C20") (pinfunction "C20_C20") (pintype "passive"))
    )
    (net (code "181") (name "unconnected-(J2-PadC21)") (class "Default")
      (node (ref "J2") (pin "C21") (pinfunction "C21_C21") (pintype "passive"))
    )
    (net (code "182") (name "unconnected-(J2-PadC22)") (class "Default")
      (node (ref "J2") (pin "C22") (pinfunction "C22_C22") (pintype "passive"))
    )
    (net (code "183") (name "unconnected-(J2-PadC23)") (class "Default")
      (node (ref "J2") (pin "C23") (pinfunction "C23_C23") (pintype "passive"))
    )
    (net (code "184") (name "unconnected-(J2-PadC24)") (class "Default")
      (node (ref "J2") (pin "C24") (pinfunction "C24_C24") (pintype "passive"))
    )
    (net (code "185") (name "unconnected-(J2-PadC25)") (class "Default")
      (node (ref "J2") (pin "C25") (pinfunction "C25_C25") (pintype "passive"))
    )
    (net (code "186") (name "unconnected-(J2-PadC26)") (class "Default")
      (node (ref "J2") (pin "C26") (pinfunction "C26_C26") (pintype "passive"))
    )
    (net (code "187") (name "unconnected-(J2-PadC27)") (class "Default")
      (node (ref "J2") (pin "C27") (pinfunction "C27_C27") (pintype "passive"))
    )
    (net (code "188") (name "unconnected-(J2-PadC28)") (class "Default")
      (node (ref "J2") (pin "C28") (pinfunction "C28_C28") (pintype "passive"))
    )
    (net (code "189") (name "unconnected-(J2-PadC29)") (class "Default")
      (node (ref "J2") (pin "C29") (pinfunction "C29_C29") (pintype "passive"))
    )
    (net (code "190") (name "unconnected-(J2-PadC30)") (class "Default")
      (node (ref "J2") (pin "C30") (pinfunction "C30_C30") (pintype "passive"))
    )
    (net (code "191") (name "unconnected-(J2-PadC31)") (class "Default")
      (node (ref "J2") (pin "C31") (pinfunction "C31_C31") (pintype "passive"))
    )
    (net (code "192") (name "unconnected-(J2-PadC32)") (class "Default")
      (node (ref "J2") (pin "C32") (pinfunction "C32_C32") (pintype "passive"))
    )
    (net (code "193") (name "unconnected-(JP1-Pad6)") (class "Default")
      (node (ref "JP1") (pin "6") (pinfunction "6_6") (pintype "passive"))
    )
    (net (code "194") (name "unconnected-(JP2-Pad6)") (class "Default")
      (node (ref "JP2") (pin "6") (pinfunction "6_6") (pintype "passive"))
    )
    (net (code "195") (name "unconnected-(PIC16-Pad2)") (class "Default")
      (node (ref "PIC16") (pin "2") (pinfunction "2_2") (pintype "passive"))
    )
    (net (code "196") (name "unconnected-(PIC16-Pad3)") (class "Default")
      (node (ref "PIC16") (pin "3") (pinfunction "3_3") (pintype "passive"))
    )
    (net (code "197") (name "unconnected-(PIC16-Pad13)") (class "Default")
      (node (ref "PIC16") (pin "13") (pinfunction "13_13") (pintype "passive"))
    )
    (net (code "198") (name "unconnected-(U$1-CLK-Pad6)") (class "Default")
      (node (ref "U$1") (pin "6") (pinfunction "CLK_6") (pintype "bidirectional"))
    )
    (net (code "199") (name "unconnected-(U$1-CS-Pad5)") (class "Default")
      (node (ref "U$1") (pin "5") (pinfunction "CS_5") (pintype "bidirectional"))
    )
    (net (code "200") (name "unconnected-(U$1-GND2-Pad15)") (class "Default")
      (node (ref "U$1") (pin "15") (pinfunction "GND2_15") (pintype "bidirectional"))
    )
    (net (code "201") (name "unconnected-(U$1-MISO-Pad7)") (class "Default")
      (node (ref "U$1") (pin "7") (pinfunction "MISO_7") (pintype "bidirectional"))
    )
    (net (code "202") (name "unconnected-(U$1-MOSI-Pad8)") (class "Default")
      (node (ref "U$1") (pin "8") (pinfunction "MOSI_8") (pintype "bidirectional"))
    )
    (net (code "203") (name "unconnected-(U$1-NAV-Pad14)") (class "Default")
      (node (ref "U$1") (pin "14") (pinfunction "NAV_14") (pintype "bidirectional"))
    )
    (net (code "204") (name "unconnected-(U$1-RX1-Pad12)") (class "Default")
      (node (ref "U$1") (pin "12") (pinfunction "RX1_12") (pintype "bidirectional"))
    )
    (net (code "205") (name "unconnected-(U$1-SCL-Pad10)") (class "Default")
      (node (ref "U$1") (pin "10") (pinfunction "SCL_10") (pintype "bidirectional"))
    )
    (net (code "206") (name "unconnected-(U$1-SDA-Pad9)") (class "Default")
      (node (ref "U$1") (pin "9") (pinfunction "SDA_9") (pintype "bidirectional"))
    )
    (net (code "207") (name "unconnected-(U$1-TX1-Pad11)") (class "Default")
      (node (ref "U$1") (pin "11") (pinfunction "TX1_11") (pintype "bidirectional"))
    )
    (net (code "208") (name "unconnected-(X1-Pad15)") (class "Default")
      (node (ref "X1") (pin "15") (pinfunction "15_15") (pintype "passive"))
    )
    (net (code "209") (name "unconnected-(X2-Pad3)") (class "Default")
      (node (ref "X2") (pin "3") (pinfunction "3_3") (pintype "passive"))
    )
    (net (code "210") (name "unconnected-(X2-Pad7)") (class "Default")
      (node (ref "X2") (pin "7") (pinfunction "7_7") (pintype "passive"))
    )
    (net (code "211") (name "unconnected-(X2-Pad10)") (class "Default")
      (node (ref "X2") (pin "10") (pinfunction "10_10") (pintype "passive"))
    )
    (net (code "212") (name "unconnected-(X2-Pad11)") (class "Default")
      (node (ref "X2") (pin "11") (pinfunction "11_11") (pintype "passive"))
    )
  )
)
